# amebot_arduino_adapter.net
KiCad netlist of a schematic drawn in EAGLE
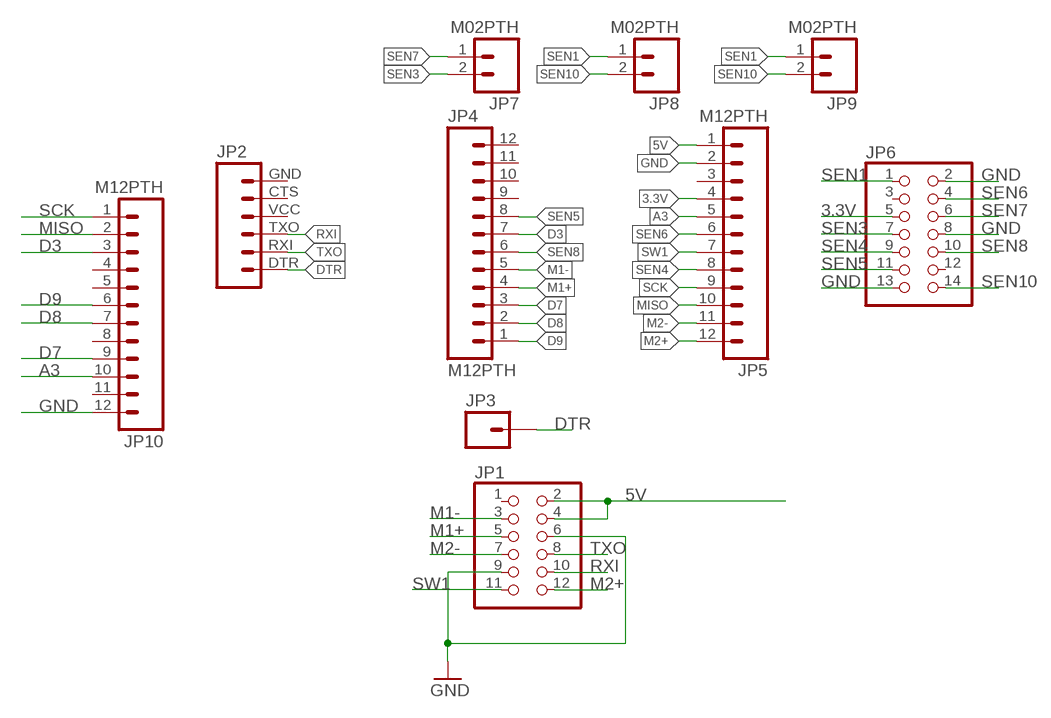
[diagram p0: schematic, sheet 1]

(export (version "E")
  (design (tool "Eeschema 10.0.6"))
  (components
    (comp (ref "JP1")
      (value "PINHD-2X6")
      (footprint "eagle-import:2X06")
      (libsource (lib "eagle-import") (part "PINHD-2X6"))
    )
    (comp (ref "JP2")
      (value "M06SIP")
      (footprint "eagle-import:1X06")
      (libsource (lib "eagle-import") (part "M06SIP"))
    )
    (comp (ref "JP3")
      (value "M01PTH_LONGPAD")
      (footprint "eagle-import:1X01_LONGPAD")
      (libsource (lib "eagle-import") (part "M01PTH_LONGPAD"))
    )
    (comp (ref "JP4")
      (value "M12PTH")
      (footprint "eagle-import:1X12")
      (libsource (lib "eagle-import") (part "M12PTH"))
    )
    (comp (ref "JP5")
      (value "M12PTH")
      (footprint "eagle-import:1X12")
      (libsource (lib "eagle-import") (part "M12PTH"))
    )
    (comp (ref "JP6")
      (value "PINHD-2X7")
      (footprint "eagle-import:2X07")
      (libsource (lib "eagle-import") (part "PINHD-2X7"))
    )
    (comp (ref "JP7")
      (value "M02PTH")
      (footprint "eagle-import:1X02")
      (libsource (lib "eagle-import") (part "M02PTH"))
    )
    (comp (ref "JP8")
      (value "M02PTH")
      (footprint "eagle-import:1X02")
      (libsource (lib "eagle-import") (part "M02PTH"))
    )
    (comp (ref "JP9")
      (value "M02PTH")
      (footprint "eagle-import:1X02")
      (libsource (lib "eagle-import") (part "M02PTH"))
    )
    (comp (ref "JP10")
      (value "M12PTH")
      (footprint "eagle-import:1X12")
      (libsource (lib "eagle-import") (part "M12PTH"))
    )
  )
  (nets
    (net (code "1") (name "3.3V") (class "Default")
      (node (ref "JP5") (pin "4") (pinfunction "4_4") (pintype "passive"))
      (node (ref "JP6") (pin "5") (pinfunction "5_5") (pintype "passive"))
    )
    (net (code "2") (name "5V") (class "Default")
      (node (ref "JP1") (pin "2") (pinfunction "2_2") (pintype "passive"))
      (node (ref "JP1") (pin "4") (pinfunction "4_4") (pintype "passive"))
      (node (ref "JP5") (pin "1") (pinfunction "1_1") (pintype "passive"))
    )
    (net (code "3") (name "A3") (class "Default")
      (node (ref "JP10") (pin "10") (pinfunction "10_10") (pintype "passive"))
      (node (ref "JP5") (pin "5") (pinfunction "5_5") (pintype "passive"))
    )
    (net (code "4") (name "D3") (class "Default")
      (node (ref "JP10") (pin "3") (pinfunction "3_3") (pintype "passive"))
      (node (ref "JP4") (pin "7") (pinfunction "7_7") (pintype "passive"))
    )
    (net (code "5") (name "D7") (class "Default")
      (node (ref "JP10") (pin "9") (pinfunction "9_9") (pintype "passive"))
      (node (ref "JP4") (pin "3") (pinfunction "3_3") (pintype "passive"))
    )
    (net (code "6") (name "D8") (class "Default")
      (node (ref "JP10") (pin "7") (pinfunction "7_7") (pintype "passive"))
      (node (ref "JP4") (pin "2") (pinfunction "2_2") (pintype "passive"))
    )
    (net (code "7") (name "D9") (class "Default")
      (node (ref "JP10") (pin "6") (pinfunction "6_6") (pintype "passive"))
      (node (ref "JP4") (pin "1") (pinfunction "1_1") (pintype "passive"))
    )
    (net (code "8") (name "DTR") (class "Default")
      (node (ref "JP2") (pin "DTR") (pinfunction "1_DTR") (pintype "passive"))
      (node (ref "JP3") (pin "1") (pinfunction "1_1") (pintype "passive"))
    )
    (net (code "9") (name "GND") (class "Default")
      (node (ref "JP1") (pin "6") (pinfunction "6_6") (pintype "passive"))
      (node (ref "JP1") (pin "9") (pinfunction "9_9") (pintype "passive"))
      (node (ref "JP10") (pin "12") (pinfunction "12_12") (pintype "passive"))
      (node (ref "JP5") (pin "2") (pinfunction "2_2") (pintype "passive"))
      (node (ref "JP6") (pin "13") (pinfunction "13_13") (pintype "passive"))
      (node (ref "JP6") (pin "2") (pinfunction "2_2") (pintype "passive"))
      (node (ref "JP6") (pin "8") (pinfunction "8_8") (pintype "passive"))
    )
    (net (code "10") (name "M1+") (class "Default")
      (node (ref "JP1") (pin "5") (pinfunction "5_5") (pintype "passive"))
      (node (ref "JP4") (pin "4") (pinfunction "4_4") (pintype "passive"))
    )
    (net (code "11") (name "M1-") (class "Default")
      (node (ref "JP1") (pin "3") (pinfunction "3_3") (pintype "passive"))
      (node (ref "JP4") (pin "5") (pinfunction "5_5") (pintype "passive"))
    )
    (net (code "12") (name "M2+") (class "Default")
      (node (ref "JP1") (pin "12") (pinfunction "12_12") (pintype "passive"))
      (node (ref "JP5") (pin "12") (pinfunction "12_12") (pintype "passive"))
    )
    (net (code "13") (name "M2-") (class "Default")
      (node (ref "JP1") (pin "7") (pinfunction "7_7") (pintype "passive"))
      (node (ref "JP5") (pin "11") (pinfunction "11_11") (pintype "passive"))
    )
    (net (code "14") (name "MISO") (class "Default")
      (node (ref "JP10") (pin "2") (pinfunction "2_2") (pintype "passive"))
      (node (ref "JP5") (pin "10") (pinfunction "10_10") (pintype "passive"))
    )
    (net (code "15") (name "RXI") (class "Default")
      (node (ref "JP1") (pin "10") (pinfunction "10_10") (pintype "passive"))
      (node (ref "JP2") (pin "TXO") (pinfunction "3_TXO") (pintype "passive"))
    )
    (net (code "16") (name "SCK") (class "Default")
      (node (ref "JP10") (pin "1") (pinfunction "1_1") (pintype "passive"))
      (node (ref "JP5") (pin "9") (pinfunction "9_9") (pintype "passive"))
    )
    (net (code "17") (name "SEN1") (class "Default")
      (node (ref "JP6") (pin "1") (pinfunction "1_1") (pintype "passive"))
      (node (ref "JP8") (pin "1") (pinfunction "1_1") (pintype "passive"))
      (node (ref "JP9") (pin "1") (pinfunction "1_1") (pintype "passive"))
    )
    (net (code "18") (name "SEN3") (class "Default")
      (node (ref "JP6") (pin "7") (pinfunction "7_7") (pintype "passive"))
      (node (ref "JP7") (pin "2") (pinfunction "2_2") (pintype "passive"))
    )
    (net (code "19") (name "SEN4") (class "Default")
      (node (ref "JP5") (pin "8") (pinfunction "8_8") (pintype "passive"))
      (node (ref "JP6") (pin "9") (pinfunction "9_9") (pintype "passive"))
    )
    (net (code "20") (name "SEN5") (class "Default")
      (node (ref "JP4") (pin "8") (pinfunction "8_8") (pintype "passive"))
      (node (ref "JP6") (pin "11") (pinfunction "11_11") (pintype "passive"))
    )
    (net (code "21") (name "SEN6") (class "Default")
      (node (ref "JP5") (pin "6") (pinfunction "6_6") (pintype "passive"))
      (node (ref "JP6") (pin "4") (pinfunction "4_4") (pintype "passive"))
    )
    (net (code "22") (name "SEN7") (class "Default")
      (node (ref "JP6") (pin "6") (pinfunction "6_6") (pintype "passive"))
      (node (ref "JP7") (pin "1") (pinfunction "1_1") (pintype "passive"))
    )
    (net (code "23") (name "SEN8") (class "Default")
      (node (ref "JP4") (pin "6") (pinfunction "6_6") (pintype "passive"))
      (node (ref "JP6") (pin "10") (pinfunction "10_10") (pintype "passive"))
    )
    (net (code "24") (name "SEN10") (class "Default")
      (node (ref "JP6") (pin "14") (pinfunction "14_14") (pintype "passive"))
      (node (ref "JP8") (pin "2") (pinfunction "2_2") (pintype "passive"))
      (node (ref "JP9") (pin "2") (pinfunction "2_2") (pintype "passive"))
    )
    (net (code "25") (name "SW1") (class "Default")
      (node (ref "JP1") (pin "11") (pinfunction "11_11") (pintype "passive"))
      (node (ref "JP5") (pin "7") (pinfunction "7_7") (pintype "passive"))
    )
    (net (code "26") (name "TXO") (class "Default")
      (node (ref "JP1") (pin "8") (pinfunction "8_8") (pintype "passive"))
      (node (ref "JP2") (pin "RXI") (pinfunction "2_RXI") (pintype "passive"))
    )
    (net (code "27") (name "unconnected-(JP1-Pad1)") (class "Default")
      (node (ref "JP1") (pin "1") (pinfunction "1_1") (pintype "passive"))
    )
    (net (code "28") (name "unconnected-(JP2-4-PadVCC)") (class "Default")
      (node (ref "JP2") (pin "VCC") (pinfunction "4_VCC") (pintype "passive"))
    )
    (net (code "29") (name "unconnected-(JP2-5-PadCTS)") (class "Default")
      (node (ref "JP2") (pin "CTS") (pinfunction "5_CTS") (pintype "passive"))
    )
    (net (code "30") (name "unconnected-(JP2-6-PadGND)") (class "Default")
      (node (ref "JP2") (pin "GND") (pinfunction "6_GND") (pintype "passive"))
    )
    (net (code "31") (name "unconnected-(JP4-Pad9)") (class "Default")
      (node (ref "JP4") (pin "9") (pinfunction "9_9") (pintype "passive"))
    )
    (net (code "32") (name "unconnected-(JP4-Pad10)") (class "Default")
      (node (ref "JP4") (pin "10") (pinfunction "10_10") (pintype "passive"))
    )
    (net (code "33") (name "unconnected-(JP4-Pad11)") (class "Default")
      (node (ref "JP4") (pin "11") (pinfunction "11_11") (pintype "passive"))
    )
    (net (code "34") (name "unconnected-(JP4-Pad12)") (class "Default")
      (node (ref "JP4") (pin "12") (pinfunction "12_12") (pintype "passive"))
    )
    (net (code "35") (name "unconnected-(JP5-Pad3)") (class "Default")
      (node (ref "JP5") (pin "3") (pinfunction "3_3") (pintype "passive"))
    )
    (net (code "36") (name "unconnected-(JP6-Pad3)") (class "Default")
      (node (ref "JP6") (pin "3") (pinfunction "3_3") (pintype "passive"))
    )
    (net (code "37") (name "unconnected-(JP6-Pad12)") (class "Default")
      (node (ref "JP6") (pin "12") (pinfunction "12_12") (pintype "passive"))
    )
    (net (code "38") (name "unconnected-(JP10-Pad4)") (class "Default")
      (node (ref "JP10") (pin "4") (pinfunction "4_4") (pintype "passive"))
    )
    (net (code "39") (name "unconnected-(JP10-Pad5)") (class "Default")
      (node (ref "JP10") (pin "5") (pinfunction "5_5") (pintype "passive"))
    )
    (net (code "40") (name "unconnected-(JP10-Pad8)") (class "Default")
      (node (ref "JP10") (pin "8") (pinfunction "8_8") (pintype "passive"))
    )
    (net (code "41") (name "unconnected-(JP10-Pad11)") (class "Default")
      (node (ref "JP10") (pin "11") (pinfunction "11_11") (pintype "passive"))
    )
  )
)
